# SNES_SCIC_IGR_D4_Takt.net
KiCad netlist of a schematic drawn in EAGLE
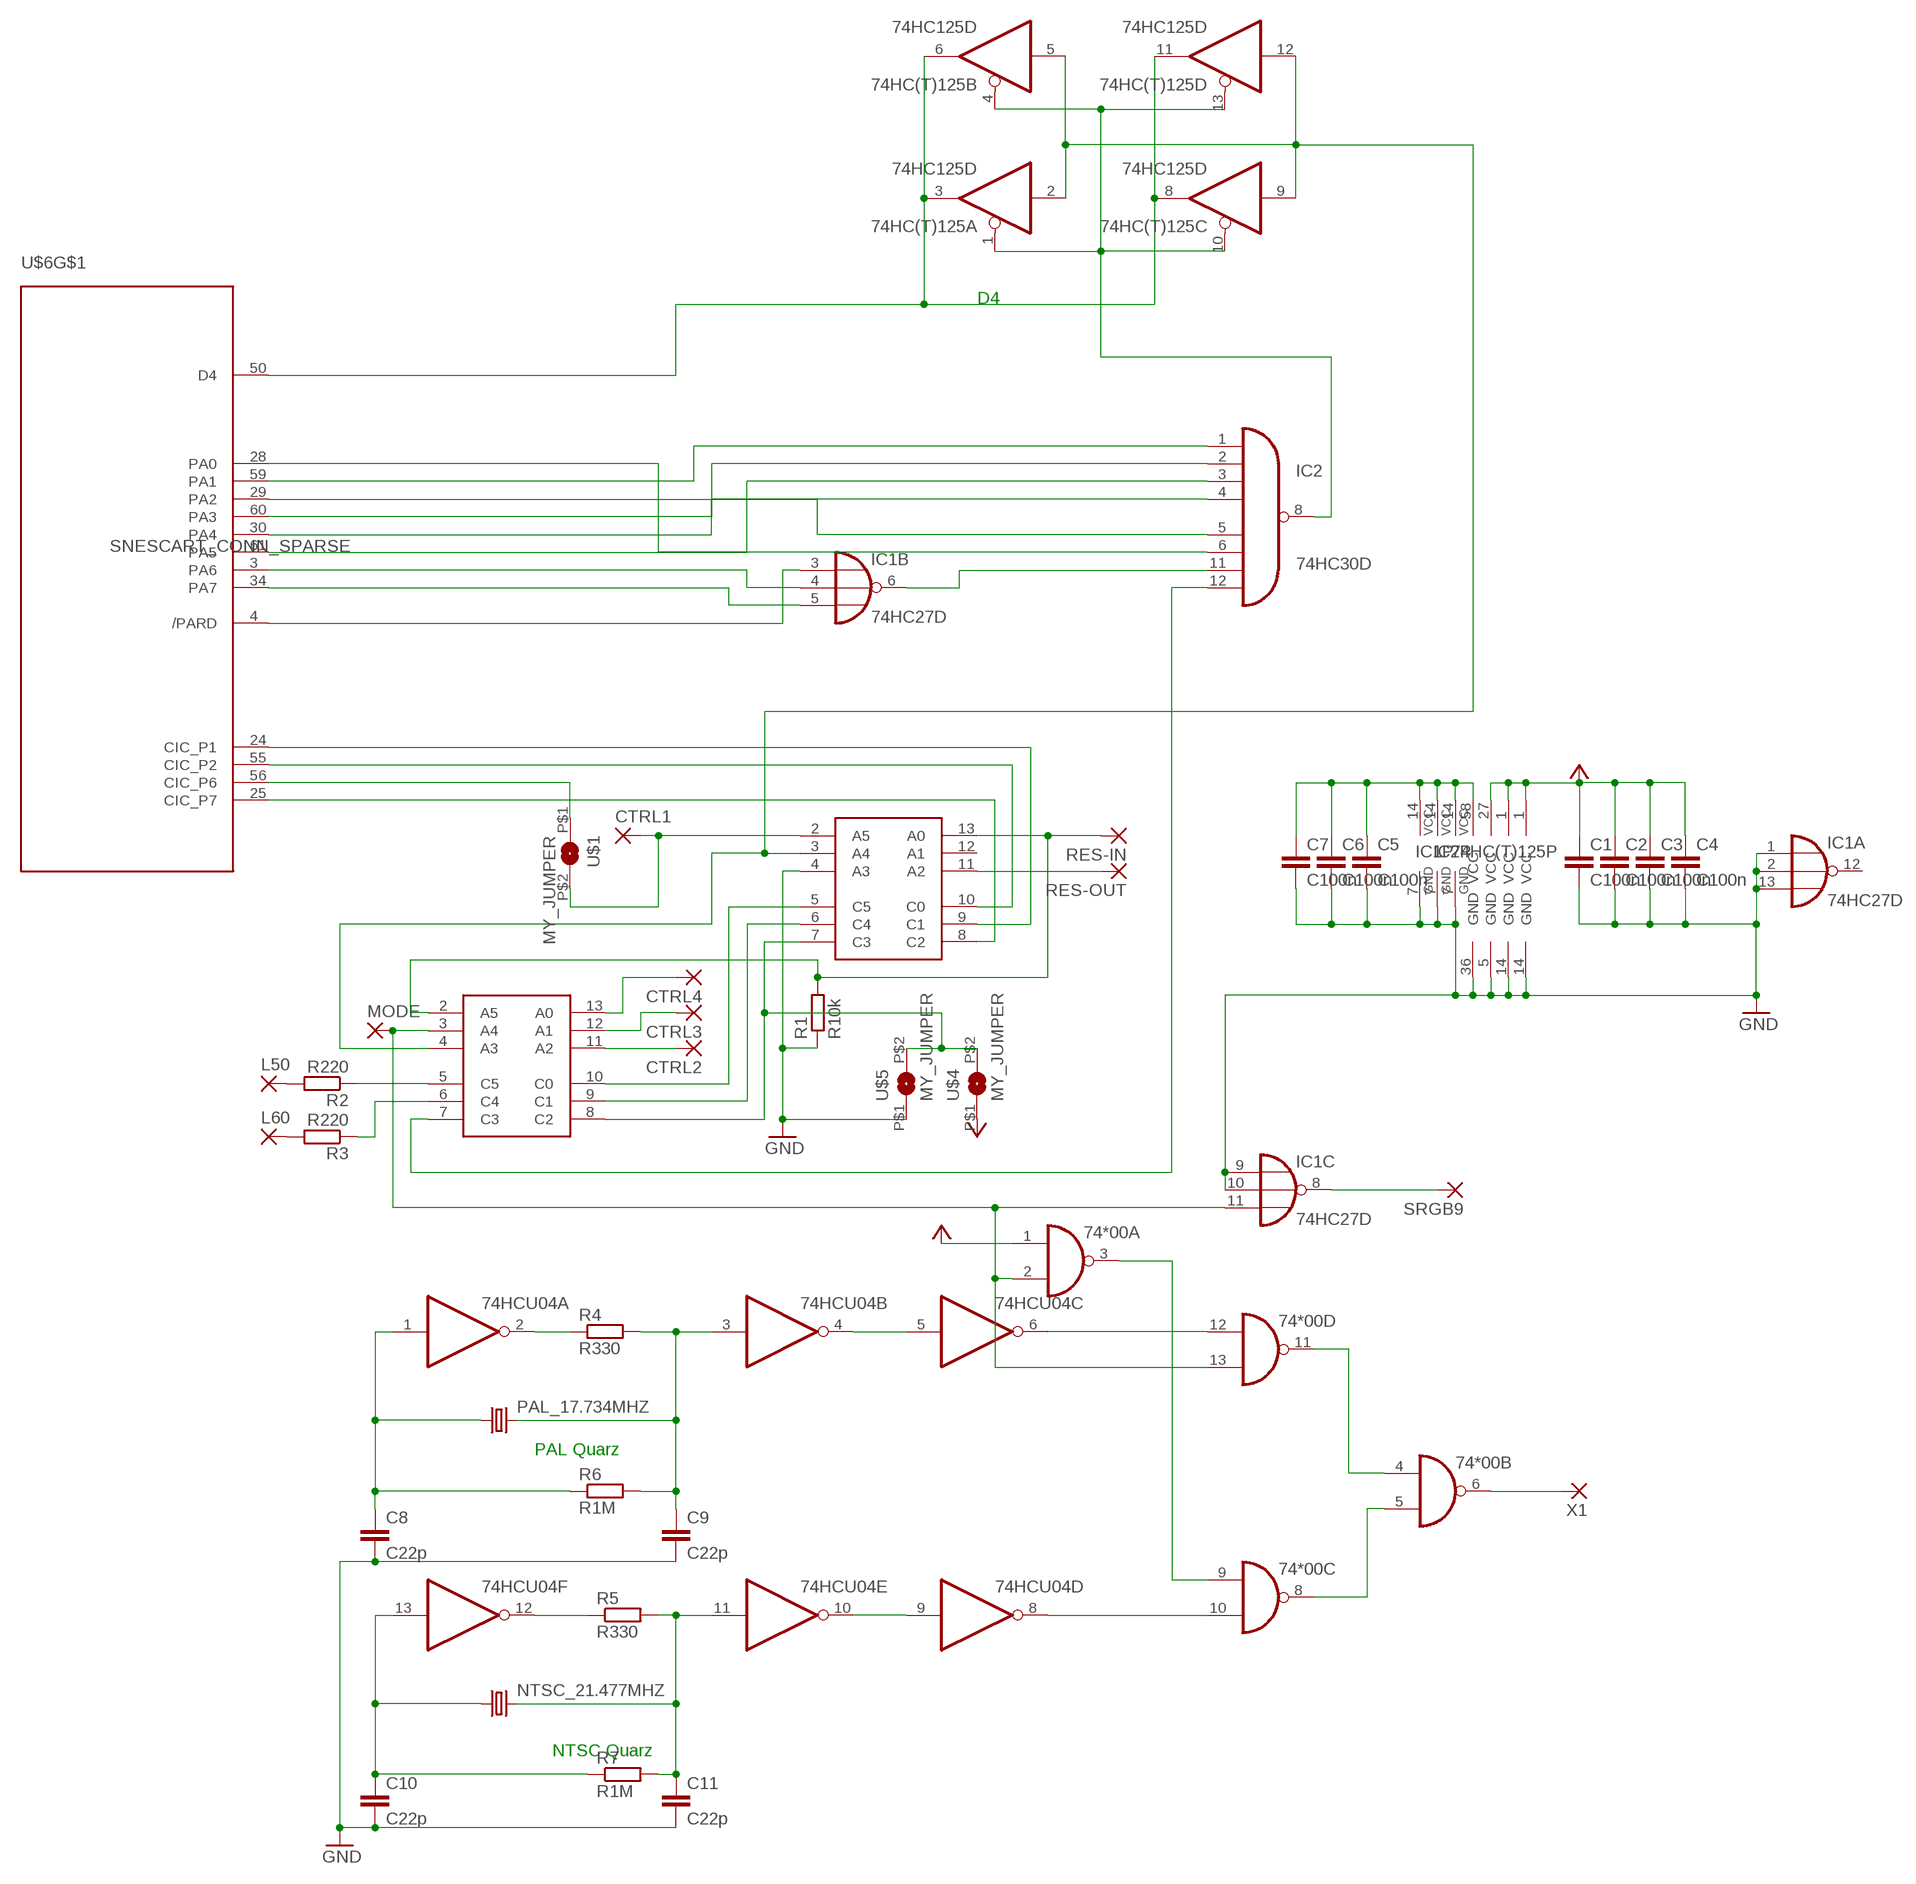
[diagram p0: schematic, sheet 1]

(export (version "E")
  (design (tool "Eeschema 10.0.6"))
  (components
    (comp (ref "74*00")
      (value "7400D")
      (footprint "eagle-import:SO14")
      (libsource (lib "eagle-import") (part "7400D"))
    )
    (comp (ref "74HC(T)125")
      (value "74HC125D")
      (footprint "eagle-import:SO14")
      (libsource (lib "eagle-import") (part "74125DHC"))
    )
    (comp (ref "74HCU04")
      (value "74HC04D")
      (footprint "eagle-import:SO14")
      (libsource (lib "eagle-import") (part "7404DHC"))
    )
    (comp (ref "C1")
      (value "C100n")
      (footprint "eagle-import:Z0805")
      (libsource (lib "eagle-import") (part "C0805"))
    )
    (comp (ref "C2")
      (value "C100n")
      (footprint "eagle-import:Z0805")
      (libsource (lib "eagle-import") (part "C0805"))
    )
    (comp (ref "C3")
      (value "C100n")
      (footprint "eagle-import:Z0805")
      (libsource (lib "eagle-import") (part "C0805"))
    )
    (comp (ref "C4")
      (value "C100n")
      (footprint "eagle-import:Z0805")
      (libsource (lib "eagle-import") (part "C0805"))
    )
    (comp (ref "C5")
      (value "C100n")
      (footprint "eagle-import:Z0805")
      (libsource (lib "eagle-import") (part "C0805"))
    )
    (comp (ref "C6")
      (value "C100n")
      (footprint "eagle-import:Z0805")
      (libsource (lib "eagle-import") (part "C0805"))
    )
    (comp (ref "C7")
      (value "C100n")
      (footprint "eagle-import:Z0805")
      (libsource (lib "eagle-import") (part "C0805"))
    )
    (comp (ref "C8")
      (value "C22p")
      (footprint "eagle-import:Z0805")
      (libsource (lib "eagle-import") (part "C0805"))
    )
    (comp (ref "C9")
      (value "C22p")
      (footprint "eagle-import:Z0805")
      (libsource (lib "eagle-import") (part "C0805"))
    )
    (comp (ref "C10")
      (value "C22p")
      (footprint "eagle-import:Z0805")
      (libsource (lib "eagle-import") (part "C0805"))
    )
    (comp (ref "C11")
      (value "C22p")
      (footprint "eagle-import:Z0805")
      (libsource (lib "eagle-import") (part "C0805"))
    )
    (comp (ref "CTRL1")
      (value "SMD2")
      (footprint "eagle-import:SMD1,27-2,54")
      (libsource (lib "eagle-import") (part "SMD2"))
    )
    (comp (ref "CTRL2")
      (value "SMD2")
      (footprint "eagle-import:SMD1,27-2,54")
      (libsource (lib "eagle-import") (part "SMD2"))
    )
    (comp (ref "CTRL3")
      (value "SMD2")
      (footprint "eagle-import:SMD1,27-2,54")
      (libsource (lib "eagle-import") (part "SMD2"))
    )
    (comp (ref "CTRL4")
      (value "SMD2")
      (footprint "eagle-import:SMD1,27-2,54")
      (libsource (lib "eagle-import") (part "SMD2"))
    )
    (comp (ref "IC1")
      (value "74HC27D")
      (footprint "eagle-import:SO14")
      (libsource (lib "eagle-import") (part "7427DHC"))
    )
    (comp (ref "IC2")
      (value "74HC30D")
      (footprint "eagle-import:SO14")
      (libsource (lib "eagle-import") (part "7430DHC"))
    )
    (comp (ref "L50")
      (value "SMD2")
      (footprint "eagle-import:SMD1,27-2,54")
      (libsource (lib "eagle-import") (part "SMD2"))
    )
    (comp (ref "L60")
      (value "SMD2")
      (footprint "eagle-import:SMD1,27-2,54")
      (libsource (lib "eagle-import") (part "SMD2"))
    )
    (comp (ref "MODE")
      (value "SMD2")
      (footprint "eagle-import:SMD1,27-2,54")
      (libsource (lib "eagle-import") (part "SMD2"))
    )
    (comp (ref "NTSC_21.477MHZ")
      (value "CRYSTALHC49UP")
      (footprint "eagle-import:HC49UP")
      (libsource (lib "eagle-import") (part "CRYSTALHC49UP"))
    )
    (comp (ref "PAL_17.734MHZ")
      (value "CRYSTALHC49UP")
      (footprint "eagle-import:HC49UP")
      (libsource (lib "eagle-import") (part "CRYSTALHC49UP"))
    )
    (comp (ref "R1")
      (value "R10k")
      (footprint "eagle-import:Z0805")
      (libsource (lib "eagle-import") (part "R0805"))
    )
    (comp (ref "R2")
      (value "R220")
      (footprint "eagle-import:Z0805")
      (libsource (lib "eagle-import") (part "R0805"))
    )
    (comp (ref "R3")
      (value "R220")
      (footprint "eagle-import:Z0805")
      (libsource (lib "eagle-import") (part "R0805"))
    )
    (comp (ref "R4")
      (value "R330")
      (footprint "eagle-import:Z0805")
      (libsource (lib "eagle-import") (part "R0805"))
    )
    (comp (ref "R5")
      (value "R330")
      (footprint "eagle-import:Z0805")
      (libsource (lib "eagle-import") (part "R0805"))
    )
    (comp (ref "R6")
      (value "R1M")
      (footprint "eagle-import:Z0805")
      (libsource (lib "eagle-import") (part "R0805"))
    )
    (comp (ref "R7")
      (value "R1M")
      (footprint "eagle-import:Z0805")
      (libsource (lib "eagle-import") (part "R0805"))
    )
    (comp (ref "RES-IN")
      (value "SMD2")
      (footprint "eagle-import:SMD1,27-2,54")
      (libsource (lib "eagle-import") (part "SMD2"))
    )
    (comp (ref "RES-OUT")
      (value "SMD2")
      (footprint "eagle-import:SMD1,27-2,54")
      (libsource (lib "eagle-import") (part "SMD2"))
    )
    (comp (ref "SRGB9")
      (value "SMD2")
      (footprint "eagle-import:SMD1,27-2,54")
      (libsource (lib "eagle-import") (part "SMD2"))
    )
    (comp (ref "U$1")
      (value "MY_JUMPER")
      (footprint "eagle-import:MYJUMP")
      (libsource (lib "eagle-import") (part "MY_JUMPER"))
    )
    (comp (ref "U$2")
      (value "PIC16F630_SIMPLE")
      (footprint "eagle-import:PIC16F630")
      (libsource (lib "eagle-import") (part "PIC16F630_SIMPLE"))
    )
    (comp (ref "U$3")
      (value "PIC16F630_SIMPLE")
      (footprint "eagle-import:PIC16F630")
      (libsource (lib "eagle-import") (part "PIC16F630_SIMPLE"))
    )
    (comp (ref "U$4")
      (value "MY_JUMPER")
      (footprint "eagle-import:MYJUMP")
      (libsource (lib "eagle-import") (part "MY_JUMPER"))
    )
    (comp (ref "U$5")
      (value "MY_JUMPER")
      (footprint "eagle-import:MYJUMP")
      (libsource (lib "eagle-import") (part "MY_JUMPER"))
    )
    (comp (ref "U$6")
      (value "SNESCART_CONN_SPARSE")
      (footprint "eagle-import:SNESCART_CONN_SPARSE")
      (libsource (lib "eagle-import") (part "SNESCART_CONN_SPARSE"))
    )
    (comp (ref "X1")
      (value "SMD2")
      (footprint "eagle-import:SMD1,27-2,54")
      (libsource (lib "eagle-import") (part "SMD2"))
    )
  )
  (nets
    (net (code "1") (name "+5V") (class "Default")
      (node (ref "74*00") (pin "1") (pinfunction "I0_1") (pintype "input"))
      (node (ref "C1") (pin "1") (pinfunction "1_1") (pintype "passive"))
      (node (ref "C2") (pin "1") (pinfunction "1_1") (pintype "passive"))
      (node (ref "C3") (pin "1") (pinfunction "1_1") (pintype "passive"))
      (node (ref "C4") (pin "1") (pinfunction "1_1") (pintype "passive"))
      (node (ref "U$2") (pin "1") (pinfunction "VCC_1") (pintype "bidirectional"))
      (node (ref "U$3") (pin "1") (pinfunction "VCC_1") (pintype "bidirectional"))
      (node (ref "U$4") (pin "P$1") (pinfunction "1_P$1") (pintype "passive"))
      (node (ref "U$6") (pin "27") (pinfunction "VCC_27") (pintype "bidirectional"))
    )
    (net (code "2") (name "GND") (class "Default")
      (node (ref "74HC(T)125") (pin "7") (pinfunction "GND_7") (pintype "power_in"))
      (node (ref "C1") (pin "2") (pinfunction "2_2") (pintype "passive"))
      (node (ref "C10") (pin "2") (pinfunction "2_2") (pintype "passive"))
      (node (ref "C11") (pin "2") (pinfunction "2_2") (pintype "passive"))
      (node (ref "C2") (pin "2") (pinfunction "2_2") (pintype "passive"))
      (node (ref "C3") (pin "2") (pinfunction "2_2") (pintype "passive"))
      (node (ref "C4") (pin "2") (pinfunction "2_2") (pintype "passive"))
      (node (ref "C5") (pin "2") (pinfunction "2_2") (pintype "passive"))
      (node (ref "C6") (pin "2") (pinfunction "2_2") (pintype "passive"))
      (node (ref "C7") (pin "2") (pinfunction "2_2") (pintype "passive"))
      (node (ref "C8") (pin "2") (pinfunction "2_2") (pintype "passive"))
      (node (ref "C9") (pin "2") (pinfunction "2_2") (pintype "passive"))
      (node (ref "IC1") (pin "1") (pinfunction "I0_1") (pintype "input"))
      (node (ref "IC1") (pin "10") (pinfunction "I1_10") (pintype "input"))
      (node (ref "IC1") (pin "13") (pinfunction "I2_13") (pintype "input"))
      (node (ref "IC1") (pin "2") (pinfunction "I1_2") (pintype "input"))
      (node (ref "IC1") (pin "7") (pinfunction "GND_7") (pintype "power_in"))
      (node (ref "IC1") (pin "9") (pinfunction "I0_9") (pintype "input"))
      (node (ref "IC2") (pin "7") (pinfunction "GND_7") (pintype "power_in"))
      (node (ref "R1") (pin "1") (pinfunction "1_1") (pintype "passive"))
      (node (ref "U$2") (pin "14") (pinfunction "GND_14") (pintype "bidirectional"))
      (node (ref "U$2") (pin "4") (pinfunction "A3_4") (pintype "bidirectional"))
      (node (ref "U$3") (pin "14") (pinfunction "GND_14") (pintype "bidirectional"))
      (node (ref "U$5") (pin "P$1") (pinfunction "1_P$1") (pintype "passive"))
      (node (ref "U$6") (pin "36") (pinfunction "GND_36") (pintype "bidirectional"))
      (node (ref "U$6") (pin "5") (pinfunction "GND_5") (pintype "bidirectional"))
    )
    (net (code "3") (name "Net-(74*00A-I1)") (class "Default")
      (node (ref "74*00") (pin "13") (pinfunction "I1_13") (pintype "input"))
      (node (ref "74*00") (pin "2") (pinfunction "I1_2") (pintype "input"))
      (node (ref "IC1") (pin "11") (pinfunction "I2_11") (pintype "input"))
      (node (ref "MODE") (pin "1") (pinfunction "P_1") (pintype "passive"))
      (node (ref "U$3") (pin "3") (pinfunction "A4_3") (pintype "bidirectional"))
    )
    (net (code "4") (name "Net-(74*00A-O)") (class "Default")
      (node (ref "74*00") (pin "3") (pinfunction "O_3") (pintype "output"))
      (node (ref "74*00") (pin "9") (pinfunction "I0_9") (pintype "input"))
    )
    (net (code "5") (name "Net-(74*00B-I0)") (class "Default")
      (node (ref "74*00") (pin "11") (pinfunction "O_11") (pintype "output"))
      (node (ref "74*00") (pin "4") (pinfunction "I0_4") (pintype "input"))
    )
    (net (code "6") (name "Net-(74*00B-I1)") (class "Default")
      (node (ref "74*00") (pin "5") (pinfunction "I1_5") (pintype "input"))
      (node (ref "74*00") (pin "8") (pinfunction "O_8") (pintype "output"))
    )
    (net (code "7") (name "Net-(74*00B-O)") (class "Default")
      (node (ref "74*00") (pin "6") (pinfunction "O_6") (pintype "output"))
      (node (ref "X1") (pin "1") (pinfunction "P_1") (pintype "passive"))
    )
    (net (code "8") (name "Net-(74*00C-I1)") (class "Default")
      (node (ref "74*00") (pin "10") (pinfunction "I1_10") (pintype "input"))
      (node (ref "74HCU04") (pin "8") (pinfunction "O_8") (pintype "output"))
    )
    (net (code "9") (name "Net-(74*00D-I0)") (class "Default")
      (node (ref "74*00") (pin "12") (pinfunction "I0_12") (pintype "input"))
      (node (ref "74HCU04") (pin "6") (pinfunction "O_6") (pintype "output"))
    )
    (net (code "10") (name "Net-(74HC(T)125A-I)") (class "Default")
      (node (ref "74HC(T)125") (pin "12") (pinfunction "I_12") (pintype "input"))
      (node (ref "74HC(T)125") (pin "2") (pinfunction "I_2") (pintype "input"))
      (node (ref "74HC(T)125") (pin "5") (pinfunction "I_5") (pintype "input"))
      (node (ref "74HC(T)125") (pin "9") (pinfunction "I_9") (pintype "input"))
      (node (ref "U$2") (pin "3") (pinfunction "A4_3") (pintype "bidirectional"))
      (node (ref "U$3") (pin "4") (pinfunction "A3_4") (pintype "bidirectional"))
    )
    (net (code "11") (name "Net-(74HC(T)125A-O)") (class "Default")
      (node (ref "74HC(T)125") (pin "11") (pinfunction "O_11") (pintype "tri_state"))
      (node (ref "74HC(T)125") (pin "3") (pinfunction "O_3") (pintype "tri_state"))
      (node (ref "74HC(T)125") (pin "6") (pinfunction "O_6") (pintype "tri_state"))
      (node (ref "74HC(T)125") (pin "8") (pinfunction "O_8") (pintype "tri_state"))
      (node (ref "U$6") (pin "50") (pinfunction "D4_50") (pintype "bidirectional"))
    )
    (net (code "12") (name "Net-(74HC(T)125A-OE)") (class "Default")
      (node (ref "74HC(T)125") (pin "1") (pinfunction "OE_1") (pintype "input"))
      (node (ref "74HC(T)125") (pin "10") (pinfunction "OE_10") (pintype "input"))
      (node (ref "74HC(T)125") (pin "13") (pinfunction "OE_13") (pintype "input"))
      (node (ref "74HC(T)125") (pin "4") (pinfunction "OE_4") (pintype "input"))
      (node (ref "IC2") (pin "8") (pinfunction "O_8") (pintype "output"))
    )
    (net (code "13") (name "Net-(74HC(T)125E-VCC)") (class "Default")
      (node (ref "74HC(T)125") (pin "14") (pinfunction "VCC_14") (pintype "power_in"))
      (node (ref "C5") (pin "1") (pinfunction "1_1") (pintype "passive"))
      (node (ref "C6") (pin "1") (pinfunction "1_1") (pintype "passive"))
      (node (ref "C7") (pin "1") (pinfunction "1_1") (pintype "passive"))
      (node (ref "IC1") (pin "14") (pinfunction "VCC_14") (pintype "power_in"))
      (node (ref "IC2") (pin "14") (pinfunction "VCC_14") (pintype "power_in"))
      (node (ref "U$6") (pin "58") (pinfunction "VCC_58") (pintype "bidirectional"))
    )
    (net (code "14") (name "Net-(74HCU04A-I)") (class "Default")
      (node (ref "74HCU04") (pin "1") (pinfunction "I_1") (pintype "input"))
      (node (ref "C8") (pin "1") (pinfunction "1_1") (pintype "passive"))
      (node (ref "PAL_17.734MHZ") (pin "1") (pinfunction "1_1") (pintype "passive"))
      (node (ref "R6") (pin "1") (pinfunction "1_1") (pintype "passive"))
    )
    (net (code "15") (name "Net-(74HCU04A-O)") (class "Default")
      (node (ref "74HCU04") (pin "2") (pinfunction "O_2") (pintype "output"))
      (node (ref "R4") (pin "1") (pinfunction "1_1") (pintype "passive"))
    )
    (net (code "16") (name "Net-(74HCU04B-I)") (class "Default")
      (node (ref "74HCU04") (pin "3") (pinfunction "I_3") (pintype "input"))
      (node (ref "C9") (pin "1") (pinfunction "1_1") (pintype "passive"))
      (node (ref "PAL_17.734MHZ") (pin "2") (pinfunction "2_2") (pintype "passive"))
      (node (ref "R4") (pin "2") (pinfunction "2_2") (pintype "passive"))
      (node (ref "R6") (pin "2") (pinfunction "2_2") (pintype "passive"))
    )
    (net (code "17") (name "Net-(74HCU04B-O)") (class "Default")
      (node (ref "74HCU04") (pin "4") (pinfunction "O_4") (pintype "output"))
      (node (ref "74HCU04") (pin "5") (pinfunction "I_5") (pintype "input"))
    )
    (net (code "18") (name "Net-(74HCU04D-I)") (class "Default")
      (node (ref "74HCU04") (pin "10") (pinfunction "O_10") (pintype "output"))
      (node (ref "74HCU04") (pin "9") (pinfunction "I_9") (pintype "input"))
    )
    (net (code "19") (name "Net-(74HCU04E-I)") (class "Default")
      (node (ref "74HCU04") (pin "11") (pinfunction "I_11") (pintype "input"))
      (node (ref "C11") (pin "1") (pinfunction "1_1") (pintype "passive"))
      (node (ref "NTSC_21.477MHZ") (pin "2") (pinfunction "2_2") (pintype "passive"))
      (node (ref "R5") (pin "2") (pinfunction "2_2") (pintype "passive"))
      (node (ref "R7") (pin "2") (pinfunction "2_2") (pintype "passive"))
    )
    (net (code "20") (name "Net-(74HCU04F-I)") (class "Default")
      (node (ref "74HCU04") (pin "13") (pinfunction "I_13") (pintype "input"))
      (node (ref "C10") (pin "1") (pinfunction "1_1") (pintype "passive"))
      (node (ref "NTSC_21.477MHZ") (pin "1") (pinfunction "1_1") (pintype "passive"))
      (node (ref "R7") (pin "1") (pinfunction "1_1") (pintype "passive"))
    )
    (net (code "21") (name "Net-(74HCU04F-O)") (class "Default")
      (node (ref "74HCU04") (pin "12") (pinfunction "O_12") (pintype "output"))
      (node (ref "R5") (pin "1") (pinfunction "1_1") (pintype "passive"))
    )
    (net (code "22") (name "Net-(CTRL1-P)") (class "Default")
      (node (ref "CTRL1") (pin "1") (pinfunction "P_1") (pintype "passive"))
      (node (ref "U$1") (pin "P$2") (pinfunction "2_P$2") (pintype "passive"))
      (node (ref "U$2") (pin "2") (pinfunction "A5_2") (pintype "bidirectional"))
    )
    (net (code "23") (name "Net-(CTRL2-P)") (class "Default")
      (node (ref "CTRL2") (pin "1") (pinfunction "P_1") (pintype "passive"))
      (node (ref "U$3") (pin "11") (pinfunction "A2_11") (pintype "bidirectional"))
    )
    (net (code "24") (name "Net-(CTRL3-P)") (class "Default")
      (node (ref "CTRL3") (pin "1") (pinfunction "P_1") (pintype "passive"))
      (node (ref "U$3") (pin "12") (pinfunction "A1_12") (pintype "bidirectional"))
    )
    (net (code "25") (name "Net-(CTRL4-P)") (class "Default")
      (node (ref "CTRL4") (pin "1") (pinfunction "P_1") (pintype "passive"))
      (node (ref "U$3") (pin "13") (pinfunction "A0_13") (pintype "bidirectional"))
    )
    (net (code "26") (name "Net-(IC1B-I0)") (class "Default")
      (node (ref "IC1") (pin "3") (pinfunction "I0_3") (pintype "input"))
      (node (ref "U$6") (pin "4") (pinfunction "/PARD_4") (pintype "bidirectional"))
    )
    (net (code "27") (name "Net-(IC1B-I1)") (class "Default")
      (node (ref "IC1") (pin "4") (pinfunction "I1_4") (pintype "input"))
      (node (ref "U$6") (pin "3") (pinfunction "PA6_3") (pintype "bidirectional"))
    )
    (net (code "28") (name "Net-(IC1B-I2)") (class "Default")
      (node (ref "IC1") (pin "5") (pinfunction "I2_5") (pintype "input"))
      (node (ref "U$6") (pin "34") (pinfunction "PA7_34") (pintype "bidirectional"))
    )
    (net (code "29") (name "Net-(IC1B-O)") (class "Default")
      (node (ref "IC1") (pin "6") (pinfunction "O_6") (pintype "output"))
      (node (ref "IC2") (pin "11") (pinfunction "I6_11") (pintype "input"))
    )
    (net (code "30") (name "Net-(IC1C-O)") (class "Default")
      (node (ref "IC1") (pin "8") (pinfunction "O_8") (pintype "output"))
      (node (ref "SRGB9") (pin "1") (pinfunction "P_1") (pintype "passive"))
    )
    (net (code "31") (name "Net-(IC2A-I0)") (class "Default")
      (node (ref "IC2") (pin "1") (pinfunction "I0_1") (pintype "input"))
      (node (ref "U$6") (pin "59") (pinfunction "PA1_59") (pintype "bidirectional"))
    )
    (net (code "32") (name "Net-(IC2A-I1)") (class "Default")
      (node (ref "IC2") (pin "2") (pinfunction "I1_2") (pintype "input"))
      (node (ref "U$6") (pin "60") (pinfunction "PA3_60") (pintype "bidirectional"))
    )
    (net (code "33") (name "Net-(IC2A-I2)") (class "Default")
      (node (ref "IC2") (pin "3") (pinfunction "I2_3") (pintype "input"))
      (node (ref "U$6") (pin "61") (pinfunction "PA5_61") (pintype "bidirectional"))
    )
    (net (code "34") (name "Net-(IC2A-I3)") (class "Default")
      (node (ref "IC2") (pin "4") (pinfunction "I3_4") (pintype "input"))
      (node (ref "U$6") (pin "30") (pinfunction "PA4_30") (pintype "bidirectional"))
    )
    (net (code "35") (name "Net-(IC2A-I4)") (class "Default")
      (node (ref "IC2") (pin "5") (pinfunction "I4_5") (pintype "input"))
      (node (ref "U$6") (pin "29") (pinfunction "PA2_29") (pintype "bidirectional"))
    )
    (net (code "36") (name "Net-(IC2A-I5)") (class "Default")
      (node (ref "IC2") (pin "6") (pinfunction "I5_6") (pintype "input"))
      (node (ref "U$6") (pin "28") (pinfunction "PA0_28") (pintype "bidirectional"))
    )
    (net (code "37") (name "Net-(IC2A-I7)") (class "Default")
      (node (ref "IC2") (pin "12") (pinfunction "I7_12") (pintype "input"))
      (node (ref "U$3") (pin "7") (pinfunction "C3_7") (pintype "bidirectional"))
    )
    (net (code "38") (name "Net-(L50-P)") (class "Default")
      (node (ref "L50") (pin "1") (pinfunction "P_1") (pintype "passive"))
      (node (ref "R2") (pin "2") (pinfunction "2_2") (pintype "passive"))
    )
    (net (code "39") (name "Net-(L60-P)") (class "Default")
      (node (ref "L60") (pin "1") (pinfunction "P_1") (pintype "passive"))
      (node (ref "R3") (pin "2") (pinfunction "2_2") (pintype "passive"))
    )
    (net (code "40") (name "Net-(RES-IN-P)") (class "Default")
      (node (ref "R1") (pin "2") (pinfunction "2_2") (pintype "passive"))
      (node (ref "RES-IN") (pin "1") (pinfunction "P_1") (pintype "passive"))
      (node (ref "U$2") (pin "13") (pinfunction "A0_13") (pintype "bidirectional"))
      (node (ref "U$3") (pin "2") (pinfunction "A5_2") (pintype "bidirectional"))
    )
    (net (code "41") (name "Net-(RES-OUT-P)") (class "Default")
      (node (ref "RES-OUT") (pin "1") (pinfunction "P_1") (pintype "passive"))
      (node (ref "U$2") (pin "11") (pinfunction "A2_11") (pintype "bidirectional"))
    )
    (net (code "42") (name "Net-(U$1-1)") (class "Default")
      (node (ref "U$1") (pin "P$1") (pinfunction "1_P$1") (pintype "passive"))
      (node (ref "U$6") (pin "56") (pinfunction "CIC_P6_56") (pintype "bidirectional"))
    )
    (net (code "43") (name "Net-(U$2A-C0)") (class "Default")
      (node (ref "U$2") (pin "10") (pinfunction "C0_10") (pintype "bidirectional"))
      (node (ref "U$6") (pin "55") (pinfunction "CIC_P2_55") (pintype "bidirectional"))
    )
    (net (code "44") (name "Net-(U$2A-C1)") (class "Default")
      (node (ref "U$2") (pin "9") (pinfunction "C1_9") (pintype "bidirectional"))
      (node (ref "U$6") (pin "24") (pinfunction "CIC_P1_24") (pintype "bidirectional"))
    )
    (net (code "45") (name "Net-(U$2A-C2)") (class "Default")
      (node (ref "U$2") (pin "8") (pinfunction "C2_8") (pintype "bidirectional"))
      (node (ref "U$6") (pin "25") (pinfunction "CIC_P7_25") (pintype "bidirectional"))
    )
    (net (code "46") (name "Net-(U$2A-C3)") (class "Default")
      (node (ref "U$2") (pin "7") (pinfunction "C3_7") (pintype "bidirectional"))
      (node (ref "U$3") (pin "8") (pinfunction "C2_8") (pintype "bidirectional"))
      (node (ref "U$4") (pin "P$2") (pinfunction "2_P$2") (pintype "passive"))
      (node (ref "U$5") (pin "P$2") (pinfunction "2_P$2") (pintype "passive"))
    )
    (net (code "47") (name "Net-(U$2A-C4)") (class "Default")
      (node (ref "U$2") (pin "6") (pinfunction "C4_6") (pintype "bidirectional"))
      (node (ref "U$3") (pin "9") (pinfunction "C1_9") (pintype "bidirectional"))
    )
    (net (code "48") (name "Net-(U$2A-C5)") (class "Default")
      (node (ref "U$2") (pin "5") (pinfunction "C5_5") (pintype "bidirectional"))
      (node (ref "U$3") (pin "10") (pinfunction "C0_10") (pintype "bidirectional"))
    )
    (net (code "49") (name "Net-(U$3A-C4)") (class "Default")
      (node (ref "R3") (pin "1") (pinfunction "1_1") (pintype "passive"))
      (node (ref "U$3") (pin "6") (pinfunction "C4_6") (pintype "bidirectional"))
    )
    (net (code "50") (name "Net-(U$3A-C5)") (class "Default")
      (node (ref "R2") (pin "1") (pinfunction "1_1") (pintype "passive"))
      (node (ref "U$3") (pin "5") (pinfunction "C5_5") (pintype "bidirectional"))
    )
    (net (code "51") (name "unconnected-(IC1A-O-Pad12)") (class "Default")
      (node (ref "IC1") (pin "12") (pinfunction "O_12") (pintype "output"))
    )
    (net (code "52") (name "unconnected-(U$2A-A1-Pad12)") (class "Default")
      (node (ref "U$2") (pin "12") (pinfunction "A1_12") (pintype "bidirectional"))
    )
  )
)
